# mcu_board.net
KiCad netlist of a schematic drawn in EAGLE
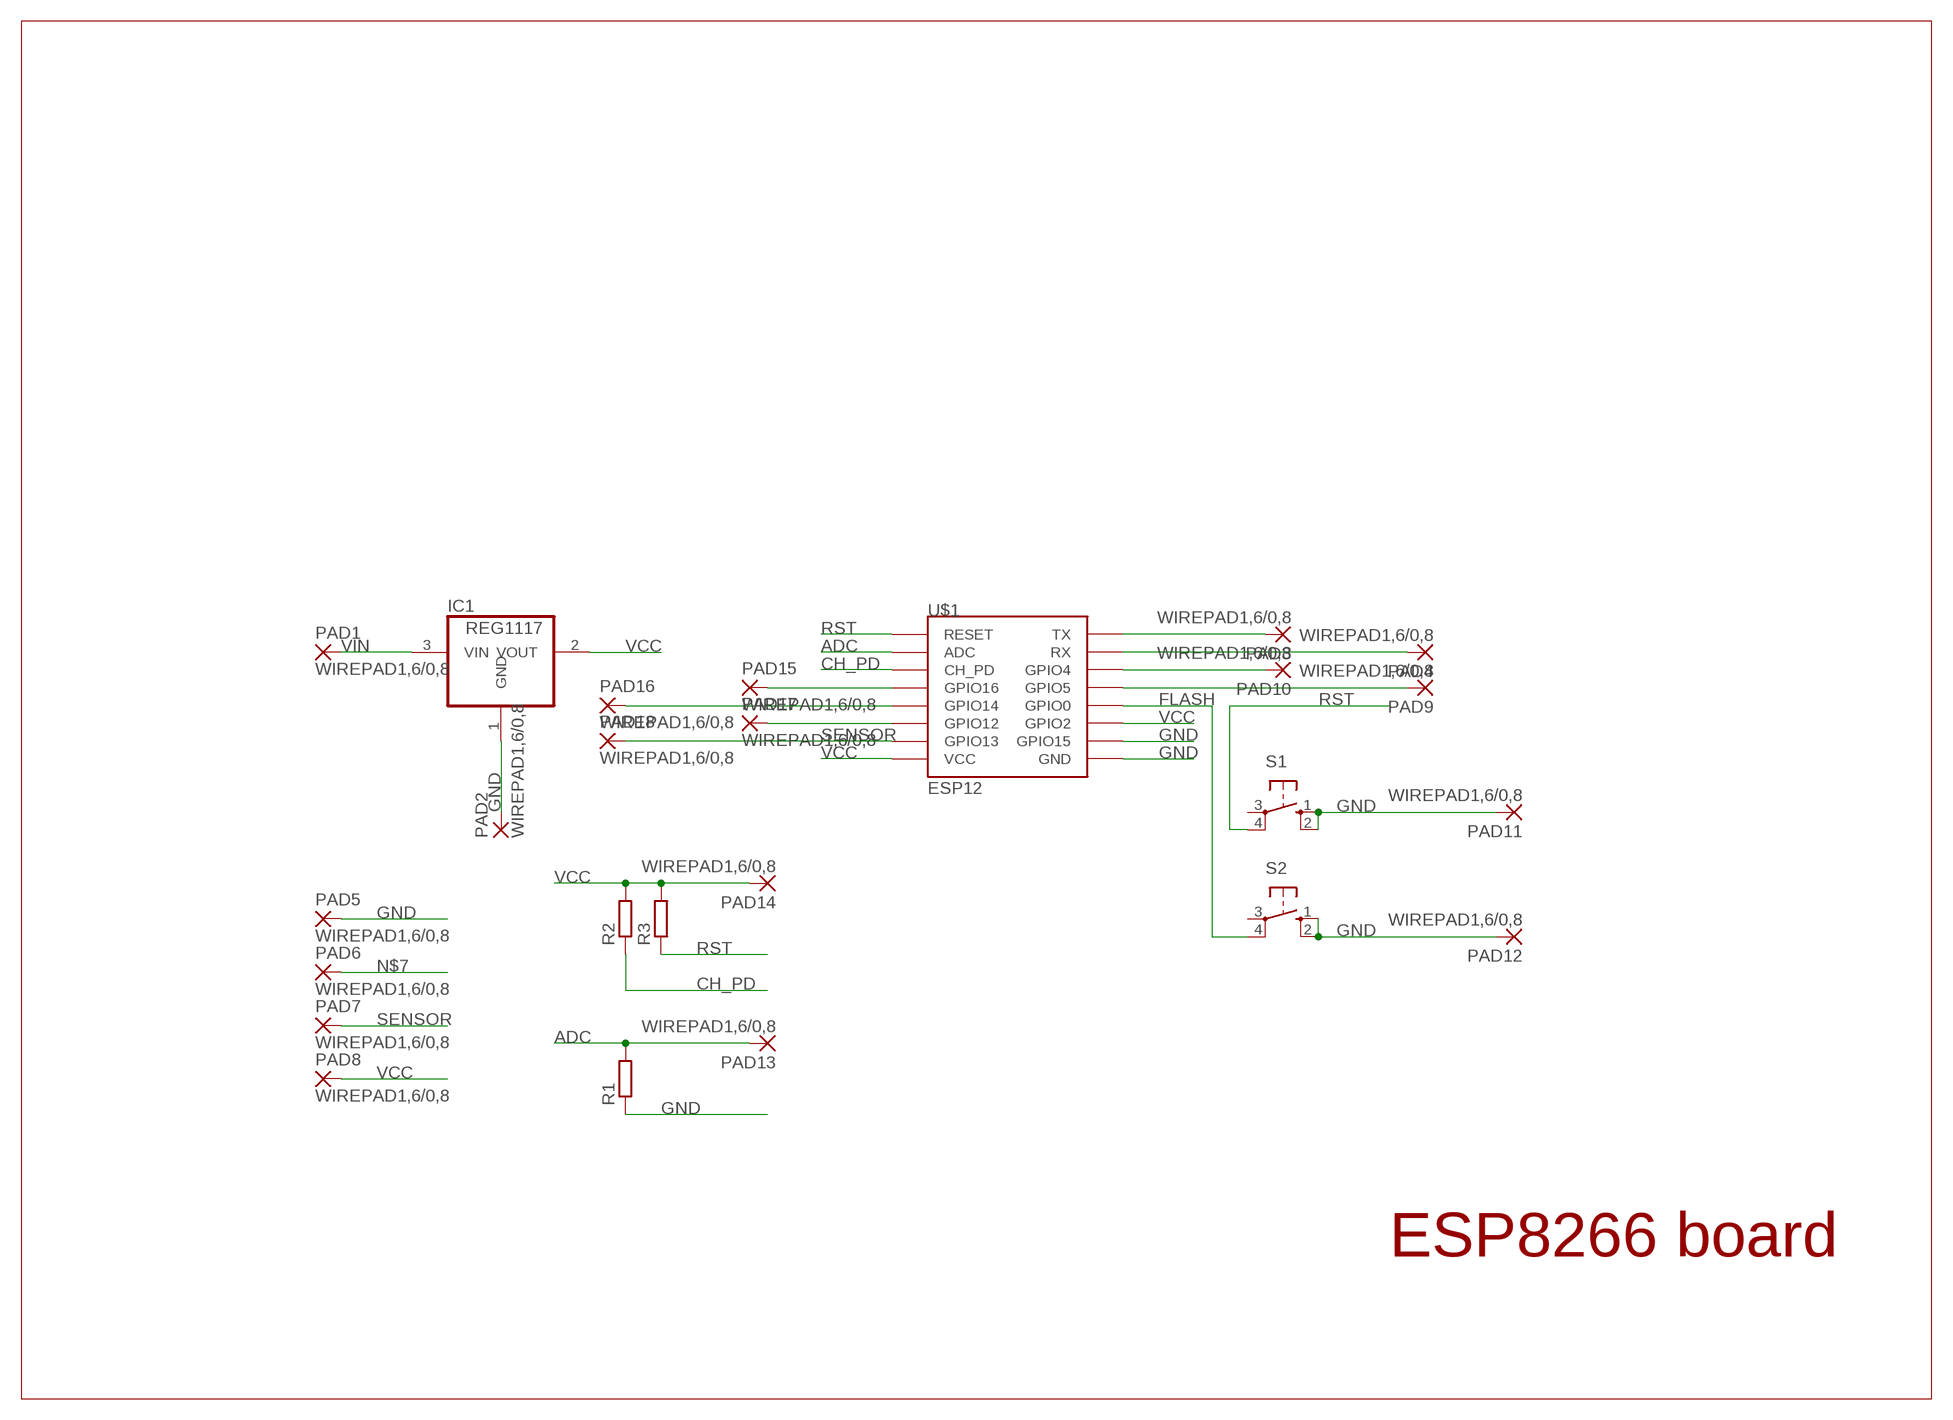
[diagram p0: schematic, sheet 1]

(export (version "E")
  (design (tool "Eeschema 10.0.6"))
  (components
    (comp (ref "IC1")
      (value "REG1117")
      (footprint "eagle-import:SOT223")
      (libsource (lib "eagle-import") (part "REG1117"))
    )
    (comp (ref "PAD1")
      (value "WIREPAD1,6/0,8")
      (footprint "eagle-import:1,6_0,8")
      (libsource (lib "eagle-import") (part "WIREPAD1,6/0,8"))
    )
    (comp (ref "PAD2")
      (value "WIREPAD1,6/0,8")
      (footprint "eagle-import:1,6_0,8")
      (libsource (lib "eagle-import") (part "WIREPAD1,6/0,8"))
    )
    (comp (ref "PAD3")
      (value "WIREPAD1,6/0,8")
      (footprint "eagle-import:1,6_0,8")
      (libsource (lib "eagle-import") (part "WIREPAD1,6/0,8"))
    )
    (comp (ref "PAD4")
      (value "WIREPAD1,6/0,8")
      (footprint "eagle-import:1,6_0,8")
      (libsource (lib "eagle-import") (part "WIREPAD1,6/0,8"))
    )
    (comp (ref "PAD5")
      (value "WIREPAD1,6/0,8")
      (footprint "eagle-import:1,6_0,8")
      (libsource (lib "eagle-import") (part "WIREPAD1,6/0,8"))
    )
    (comp (ref "PAD6")
      (value "WIREPAD1,6/0,8")
      (footprint "eagle-import:1,6_0,8")
      (libsource (lib "eagle-import") (part "WIREPAD1,6/0,8"))
    )
    (comp (ref "PAD7")
      (value "WIREPAD1,6/0,8")
      (footprint "eagle-import:1,6_0,8")
      (libsource (lib "eagle-import") (part "WIREPAD1,6/0,8"))
    )
    (comp (ref "PAD8")
      (value "WIREPAD1,6/0,8")
      (footprint "eagle-import:1,6_0,8")
      (libsource (lib "eagle-import") (part "WIREPAD1,6/0,8"))
    )
    (comp (ref "PAD9")
      (value "WIREPAD1,6/0,8")
      (footprint "eagle-import:1,6_0,8")
      (libsource (lib "eagle-import") (part "WIREPAD1,6/0,8"))
    )
    (comp (ref "PAD10")
      (value "WIREPAD1,6/0,8")
      (footprint "eagle-import:1,6_0,8")
      (libsource (lib "eagle-import") (part "WIREPAD1,6/0,8"))
    )
    (comp (ref "PAD11")
      (value "WIREPAD1,6/0,8")
      (footprint "eagle-import:1,6_0,8")
      (libsource (lib "eagle-import") (part "WIREPAD1,6/0,8"))
    )
    (comp (ref "PAD12")
      (value "WIREPAD1,6/0,8")
      (footprint "eagle-import:1,6_0,8")
      (libsource (lib "eagle-import") (part "WIREPAD1,6/0,8"))
    )
    (comp (ref "PAD13")
      (value "WIREPAD1,6/0,8")
      (footprint "eagle-import:1,6_0,8")
      (libsource (lib "eagle-import") (part "WIREPAD1,6/0,8"))
    )
    (comp (ref "PAD14")
      (value "WIREPAD1,6/0,8")
      (footprint "eagle-import:1,6_0,8")
      (libsource (lib "eagle-import") (part "WIREPAD1,6/0,8"))
    )
    (comp (ref "PAD15")
      (value "WIREPAD1,6/0,8")
      (footprint "eagle-import:1,6_0,8")
      (libsource (lib "eagle-import") (part "WIREPAD1,6/0,8"))
    )
    (comp (ref "PAD16")
      (value "WIREPAD1,6/0,8")
      (footprint "eagle-import:1,6_0,8")
      (libsource (lib "eagle-import") (part "WIREPAD1,6/0,8"))
    )
    (comp (ref "PAD17")
      (value "WIREPAD1,6/0,8")
      (footprint "eagle-import:1,6_0,8")
      (libsource (lib "eagle-import") (part "WIREPAD1,6/0,8"))
    )
    (comp (ref "PAD18")
      (value "WIREPAD1,6/0,8")
      (footprint "eagle-import:1,6_0,8")
      (libsource (lib "eagle-import") (part "WIREPAD1,6/0,8"))
    )
    (comp (ref "R1")
      (value "R-EU_M0805")
      (footprint "eagle-import:M0805")
      (libsource (lib "eagle-import") (part "R-EU_M0805"))
    )
    (comp (ref "R2")
      (value "R-EU_M0805")
      (footprint "eagle-import:M0805")
      (libsource (lib "eagle-import") (part "R-EU_M0805"))
    )
    (comp (ref "R3")
      (value "R-EU_M0805")
      (footprint "eagle-import:M0805")
      (libsource (lib "eagle-import") (part "R-EU_M0805"))
    )
    (comp (ref "S1")
      (value "10-XX")
      (footprint "eagle-import:B3F-10XX")
      (fields (field (name "MPN") "B3F-1000"))
      (libsource (lib "eagle-import") (part "10-XX"))
    )
    (comp (ref "S2")
      (value "10-XX")
      (footprint "eagle-import:B3F-10XX")
      (fields (field (name "MPN") "B3F-1000"))
      (libsource (lib "eagle-import") (part "10-XX"))
    )
    (comp (ref "U$1")
      (value "ESP12")
      (footprint "eagle-import:ESP12")
      (libsource (lib "eagle-import") (part "ESP12"))
    )
  )
  (nets
    (net (code "1") (name "/ADC") (class "Default")
      (node (ref "PAD13") (pin "1") (pinfunction "P_1") (pintype "passive"))
      (node (ref "R1") (pin "2") (pinfunction "2_2") (pintype "passive"))
      (node (ref "U$1") (pin "ADC") (pinfunction "ADC_ADC") (pintype "bidirectional"))
    )
    (net (code "2") (name "/CH_PD") (class "Default")
      (node (ref "R2") (pin "1") (pinfunction "1_1") (pintype "passive"))
      (node (ref "U$1") (pin "CH_PD") (pinfunction "CH_PD_CH_PD") (pintype "bidirectional"))
    )
    (net (code "3") (name "/FLASH") (class "Default")
      (node (ref "S2") (pin "4") (pinfunction "P1_4") (pintype "passive"))
      (node (ref "U$1") (pin "GPIO0") (pinfunction "GPIO0_GPIO0") (pintype "bidirectional"))
    )
    (net (code "4") (name "/GND") (class "Default")
      (node (ref "IC1") (pin "1") (pinfunction "GND_1") (pintype "power_in"))
      (node (ref "PAD11") (pin "1") (pinfunction "P_1") (pintype "passive"))
      (node (ref "PAD12") (pin "1") (pinfunction "P_1") (pintype "passive"))
      (node (ref "PAD2") (pin "1") (pinfunction "P_1") (pintype "passive"))
      (node (ref "PAD5") (pin "1") (pinfunction "P_1") (pintype "passive"))
      (node (ref "R1") (pin "1") (pinfunction "1_1") (pintype "passive"))
      (node (ref "S1") (pin "1") (pinfunction "S_1") (pintype "passive"))
      (node (ref "S1") (pin "2") (pinfunction "S1_2") (pintype "passive"))
      (node (ref "S2") (pin "1") (pinfunction "S_1") (pintype "passive"))
      (node (ref "S2") (pin "2") (pinfunction "S1_2") (pintype "passive"))
      (node (ref "U$1") (pin "GND") (pinfunction "GND_GND") (pintype "bidirectional"))
      (node (ref "U$1") (pin "GPIO15") (pinfunction "GPIO15_GPIO15") (pintype "bidirectional"))
    )
    (net (code "5") (name "/N$7") (class "Default")
      (node (ref "PAD6") (pin "1") (pinfunction "P_1") (pintype "passive"))
    )
    (net (code "6") (name "/RST") (class "Default")
      (node (ref "R3") (pin "1") (pinfunction "1_1") (pintype "passive"))
      (node (ref "S1") (pin "4") (pinfunction "P1_4") (pintype "passive"))
      (node (ref "U$1") (pin "RESET") (pinfunction "RESET_RESET") (pintype "bidirectional"))
    )
    (net (code "7") (name "/SENSOR") (class "Default")
      (node (ref "PAD18") (pin "1") (pinfunction "P_1") (pintype "passive"))
      (node (ref "PAD7") (pin "1") (pinfunction "P_1") (pintype "passive"))
      (node (ref "U$1") (pin "GPIO13") (pinfunction "GPIO13_GPIO13") (pintype "bidirectional"))
    )
    (net (code "8") (name "/VCC") (class "Default")
      (node (ref "IC1") (pin "2") (pinfunction "VOUT_2") (pintype "output"))
      (node (ref "PAD14") (pin "1") (pinfunction "P_1") (pintype "passive"))
      (node (ref "PAD8") (pin "1") (pinfunction "P_1") (pintype "passive"))
      (node (ref "R2") (pin "2") (pinfunction "2_2") (pintype "passive"))
      (node (ref "R3") (pin "2") (pinfunction "2_2") (pintype "passive"))
      (node (ref "U$1") (pin "GPIO2") (pinfunction "GPIO2_GPIO2") (pintype "bidirectional"))
      (node (ref "U$1") (pin "VCC") (pinfunction "VCC_VCC") (pintype "bidirectional"))
    )
    (net (code "9") (name "/VIN") (class "Default")
      (node (ref "IC1") (pin "3") (pinfunction "VIN_3") (pintype "input"))
      (node (ref "PAD1") (pin "1") (pinfunction "P_1") (pintype "passive"))
    )
    (net (code "10") (name "Net-(PAD3-P)") (class "Default")
      (node (ref "PAD3") (pin "1") (pinfunction "P_1") (pintype "passive"))
      (node (ref "U$1") (pin "TX") (pinfunction "TX_TX") (pintype "bidirectional"))
    )
    (net (code "11") (name "Net-(PAD4-P)") (class "Default")
      (node (ref "PAD4") (pin "1") (pinfunction "P_1") (pintype "passive"))
      (node (ref "U$1") (pin "RX") (pinfunction "RX_RX") (pintype "bidirectional"))
    )
    (net (code "12") (name "Net-(PAD9-P)") (class "Default")
      (node (ref "PAD9") (pin "1") (pinfunction "P_1") (pintype "passive"))
      (node (ref "U$1") (pin "GPIO5") (pinfunction "GPIO5_GPIO5") (pintype "bidirectional"))
    )
    (net (code "13") (name "Net-(PAD10-P)") (class "Default")
      (node (ref "PAD10") (pin "1") (pinfunction "P_1") (pintype "passive"))
      (node (ref "U$1") (pin "GPIO4") (pinfunction "GPIO4_GPIO4") (pintype "bidirectional"))
    )
    (net (code "14") (name "Net-(PAD15-P)") (class "Default")
      (node (ref "PAD15") (pin "1") (pinfunction "P_1") (pintype "passive"))
      (node (ref "U$1") (pin "GPIO16") (pinfunction "GPIO16_GPIO16") (pintype "bidirectional"))
    )
    (net (code "15") (name "Net-(PAD16-P)") (class "Default")
      (node (ref "PAD16") (pin "1") (pinfunction "P_1") (pintype "passive"))
      (node (ref "U$1") (pin "GPIO14") (pinfunction "GPIO14_GPIO14") (pintype "bidirectional"))
    )
    (net (code "16") (name "Net-(PAD17-P)") (class "Default")
      (node (ref "PAD17") (pin "1") (pinfunction "P_1") (pintype "passive"))
      (node (ref "U$1") (pin "GPIO12") (pinfunction "GPIO12_GPIO12") (pintype "bidirectional"))
    )
    (net (code "17") (name "unconnected-(S1-P-Pad3)") (class "Default")
      (node (ref "S1") (pin "3") (pinfunction "P_3") (pintype "passive"))
    )
    (net (code "18") (name "unconnected-(S2-P-Pad3)") (class "Default")
      (node (ref "S2") (pin "3") (pinfunction "P_3") (pintype "passive"))
    )
  )
)
